# SCH_nfc-card_2024-05-13.net
KiCad netlist of a schematic drawn in EasyEDA
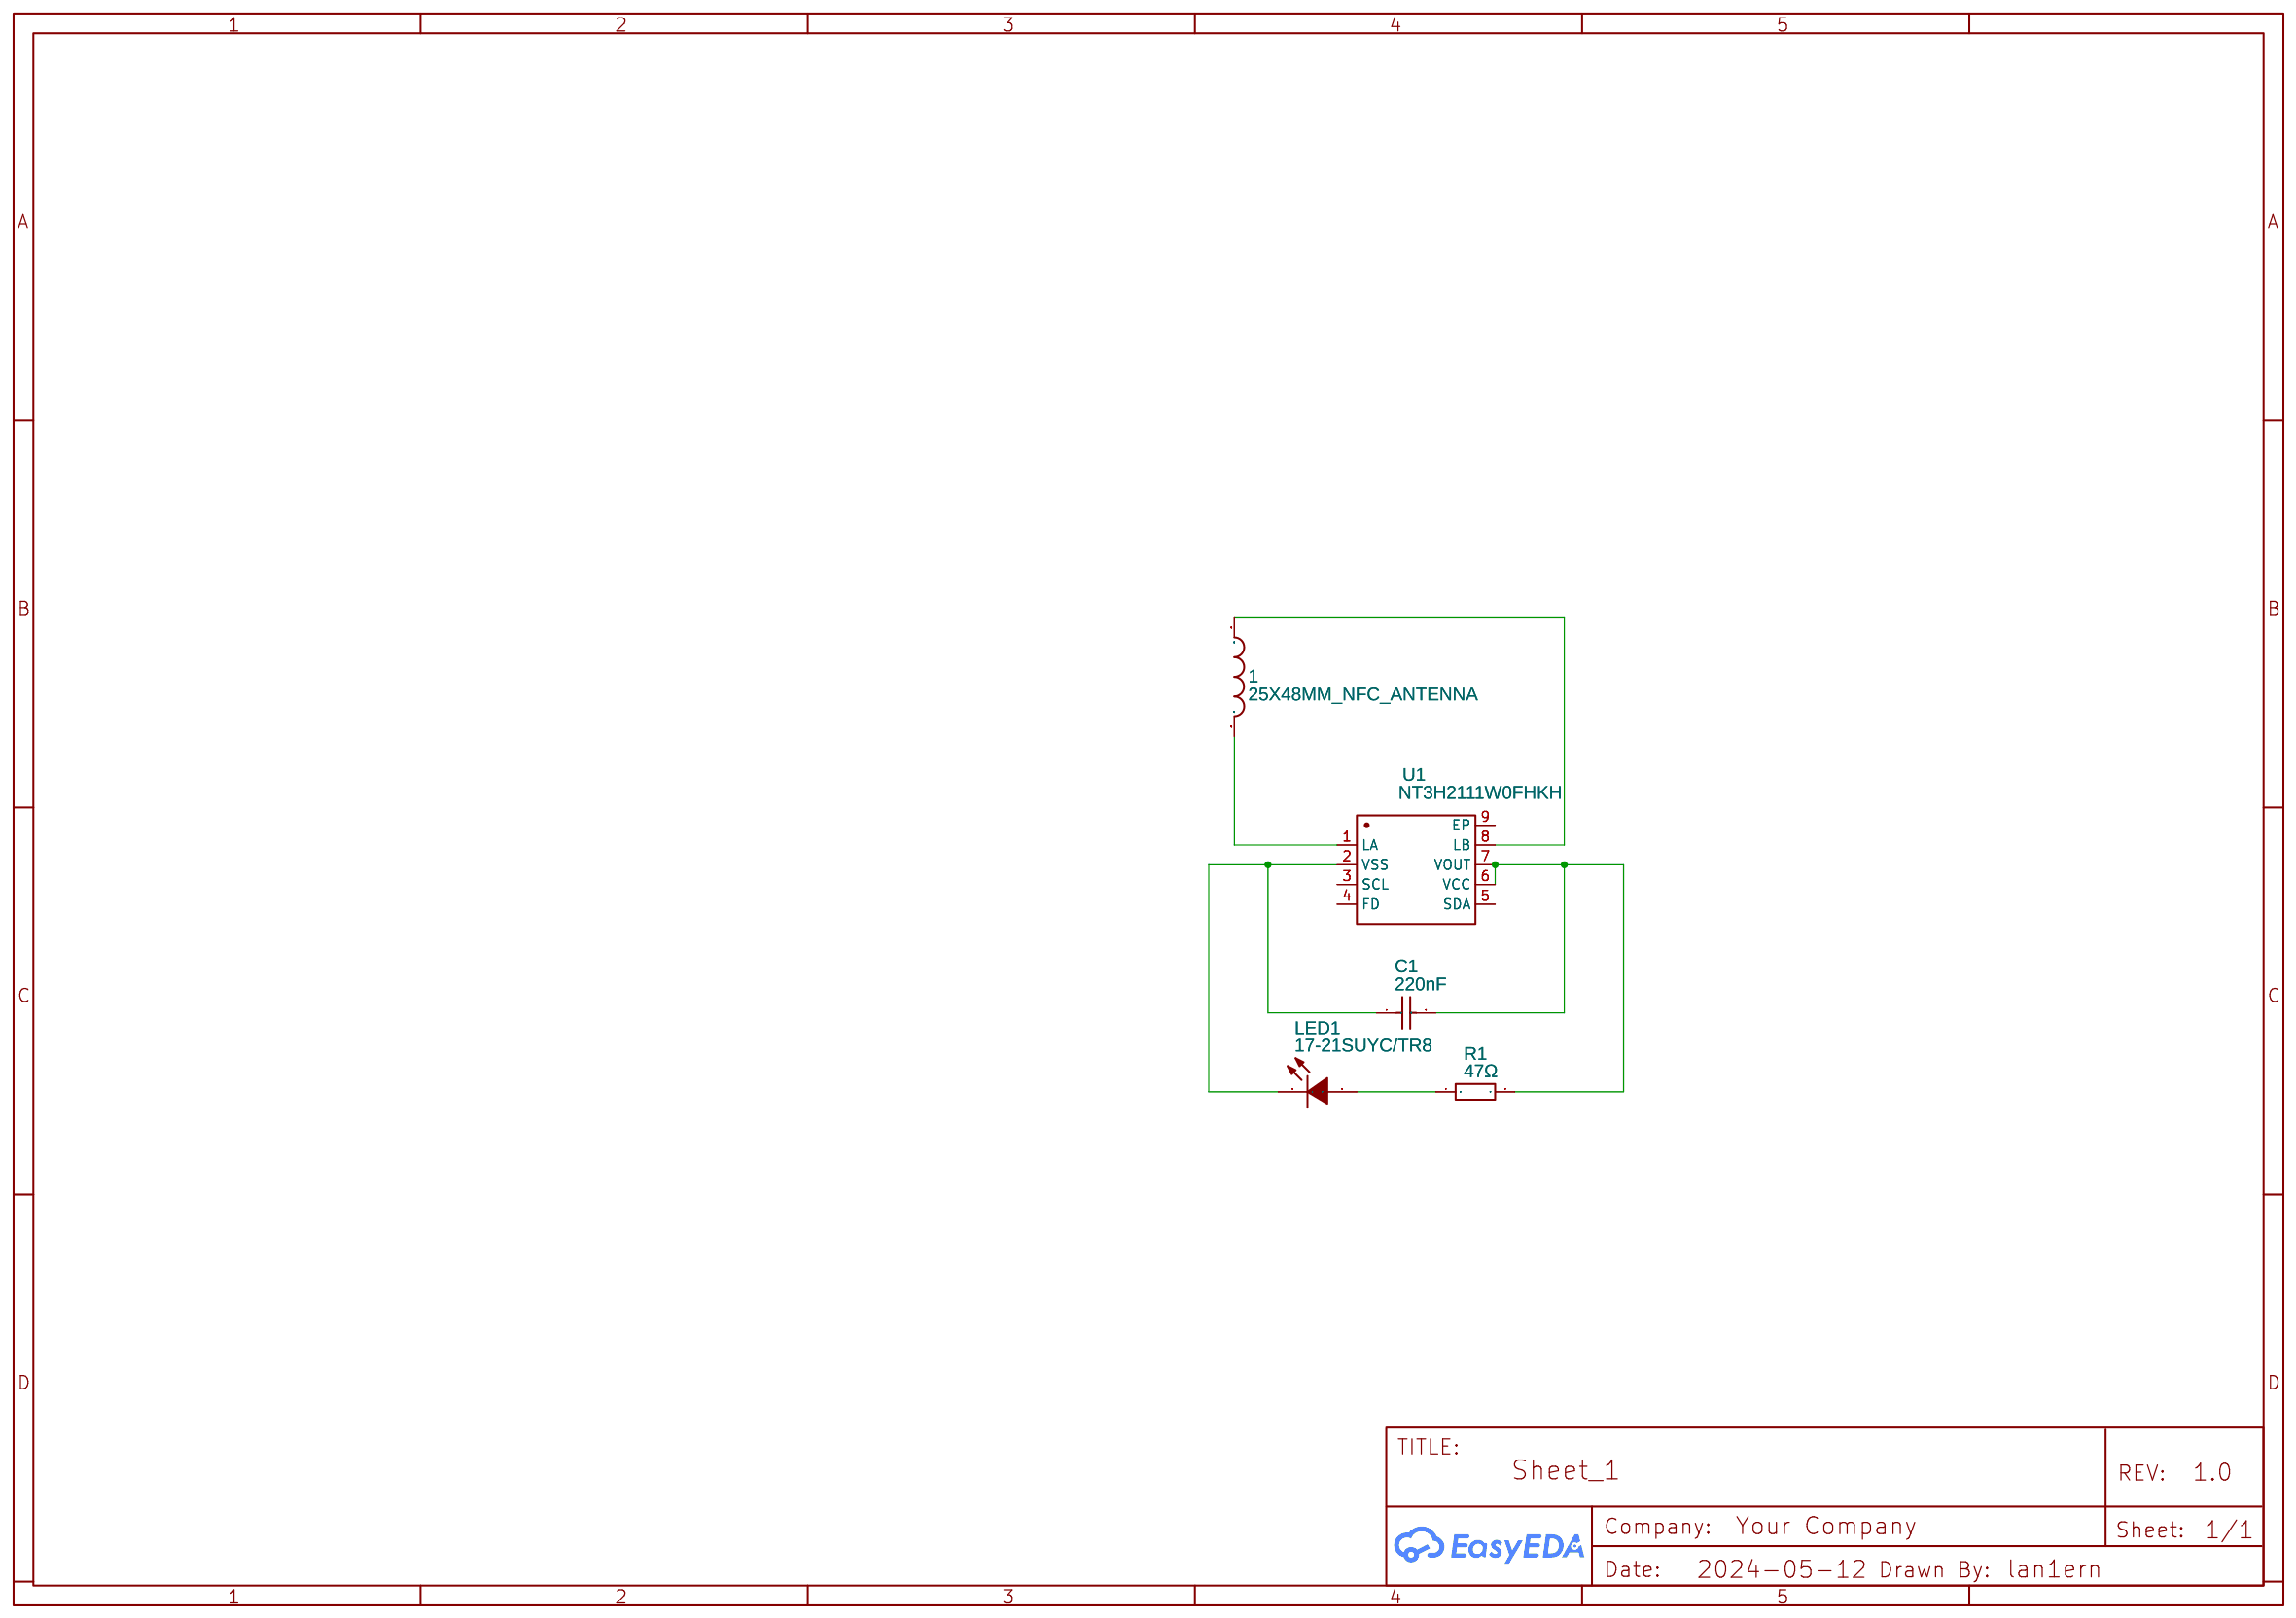
[diagram p0: schematic sheet]

(export (version "E")
  (design (tool "Eeschema 10.0.6"))
  (components
    (comp (ref "1") (value "25X48MM_NFC_ANTENNA") (libsource (lib "") (part "25X48MM_NFC_ANTENNA")))
    (comp (ref "C1")
      (value "220nF")
      (fields
        (field (name "Manufacturer Part") "CL10B224KA8NNNC")
        (field (name "Manufacturer") "SAMSUNG(三星)")
      )
      (libsource (lib "") (part "CL10B224KA8NNNC"))
    )
    (comp (ref "LED1")
      (value "17-21SUYC/TR8")
      (fields (field (name "Manufacturer Part") "KT-0805黄灯") (field (name "Manufacturer") "KENTO"))
      (libsource (lib "") (part "17-21SUYC/TR8"))
    )
    (comp (ref "R1")
      (value "47Ω")
      (fields
        (field (name "Manufacturer Part") "0603WAF470JT5E")
        (field (name "Manufacturer") "UNI-ROYAL(厚声)")
      )
      (libsource (lib "") (part "0603WAF470JT5E"))
    )
    (comp (ref "U1")
      (value "NT3H2111W0FHKH")
      (fields (field (name "Manufacturer") "NXP(恩智浦)"))
      (libsource (lib "") (part "NT3H2111W0FHKH"))
    )
  )
  (nets
    (net (code "1") (name "Net-(LED1-+)") (class "Default")
      (node (ref "LED1") (pin "1") (pinfunction "+_1") (pintype "unspecified"))
      (node (ref "R1") (pin "1") (pinfunction "1_1") (pintype "input"))
    )
    (net (code "2") (name "Net-(LED1--)") (class "Default")
      (node (ref "C1") (pin "1") (pinfunction "1_1") (pintype "input"))
      (node (ref "LED1") (pin "2") (pinfunction "-_2") (pintype "unspecified"))
      (node (ref "U1") (pin "2") (pinfunction "VSS_2") (pintype "unspecified"))
    )
    (net (code "3") (name "Net-(U1-LA)") (class "Default")
      (node (ref "1") (pin "P$2") (pinfunction "P$2_P$2") (pintype "bidirectional"))
      (node (ref "U1") (pin "1") (pinfunction "LA_1") (pintype "unspecified"))
    )
    (net (code "4") (name "Net-(U1-LB)") (class "Default")
      (node (ref "1") (pin "P$1") (pinfunction "P$1_P$1") (pintype "bidirectional"))
      (node (ref "U1") (pin "8") (pinfunction "LB_8") (pintype "unspecified"))
    )
    (net (code "5") (name "Net-(U1-VCC)") (class "Default")
      (node (ref "C1") (pin "2") (pinfunction "2_2") (pintype "input"))
      (node (ref "R1") (pin "2") (pinfunction "2_2") (pintype "input"))
      (node (ref "U1") (pin "6") (pinfunction "VCC_6") (pintype "unspecified"))
      (node (ref "U1") (pin "7") (pinfunction "VOUT_7") (pintype "unspecified"))
    )
    (net (code "6") (name "unconnected-(U1-EP-Pad9)") (class "Default")
      (node (ref "U1") (pin "9") (pinfunction "EP_9") (pintype "unspecified"))
    )
    (net (code "7") (name "unconnected-(U1-FD-Pad4)") (class "Default")
      (node (ref "U1") (pin "4") (pinfunction "FD_4") (pintype "unspecified"))
    )
    (net (code "8") (name "unconnected-(U1-SCL-Pad3)") (class "Default")
      (node (ref "U1") (pin "3") (pinfunction "SCL_3") (pintype "unspecified"))
    )
    (net (code "9") (name "unconnected-(U1-SDA-Pad5)") (class "Default")
      (node (ref "U1") (pin "5") (pinfunction "SDA_5") (pintype "unspecified"))
    )
  )
)
